# cp2102_esp32.net
KiCad netlist of a schematic drawn in EAGLE
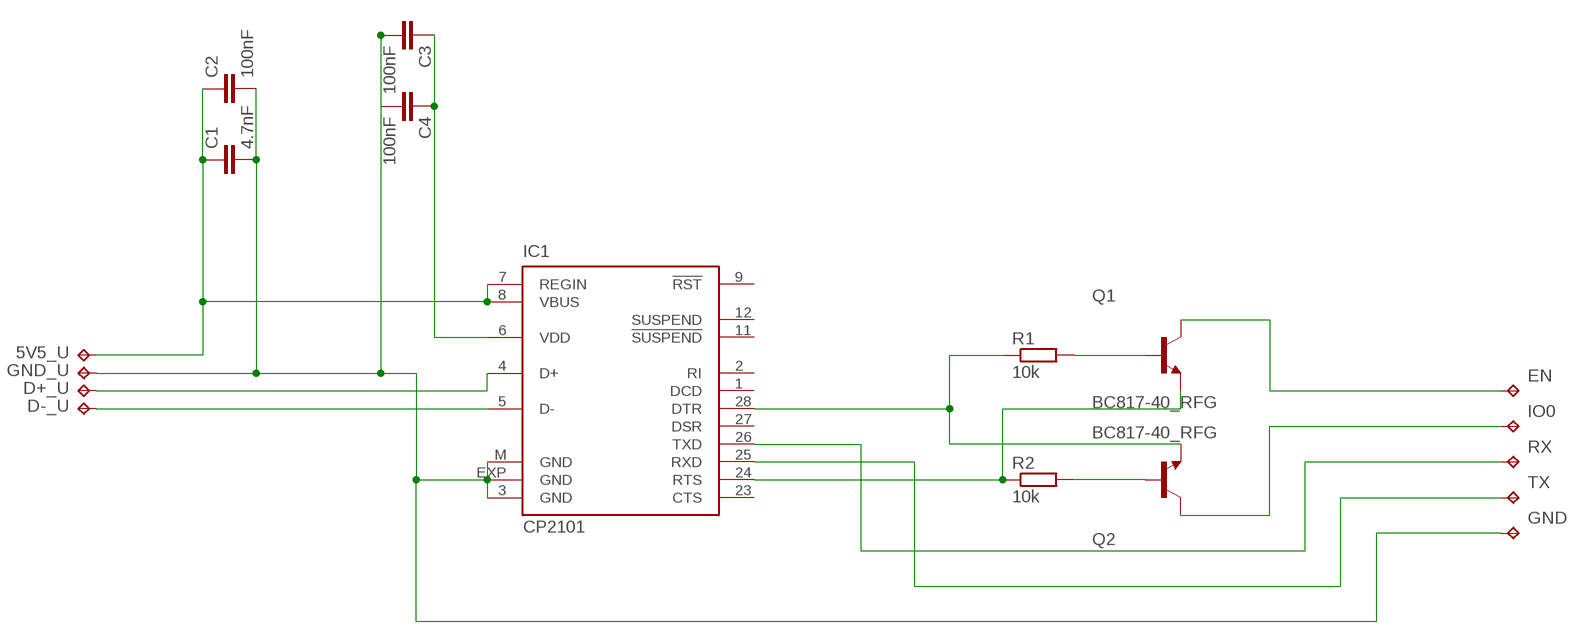
[diagram p0: schematic, sheet 1]

(export (version "E")
  (design (tool "Eeschema 10.0.6"))
  (components
    (comp (ref "5V5_U")
      (value "TPB1,27")
      (footprint "eagle-import:B1,27")
      (libsource (lib "eagle-import") (part "TPB1,27"))
    )
    (comp (ref "C1")
      (value "4.7nF")
      (footprint "eagle-import:C0603")
      (libsource (lib "eagle-import") (part "C-EUC0603"))
    )
    (comp (ref "C2")
      (value "100nF")
      (footprint "eagle-import:C0603")
      (libsource (lib "eagle-import") (part "C-EUC0603"))
    )
    (comp (ref "C3")
      (value "100nF")
      (footprint "eagle-import:C0603")
      (libsource (lib "eagle-import") (part "C-EUC0603"))
    )
    (comp (ref "C4")
      (value "100nF")
      (footprint "eagle-import:C0603")
      (libsource (lib "eagle-import") (part "C-EUC0603"))
    )
    (comp (ref "D+_U")
      (value "TPB1,27")
      (footprint "eagle-import:B1,27")
      (libsource (lib "eagle-import") (part "TPB1,27"))
    )
    (comp (ref "D-_U")
      (value "TPB1,27")
      (footprint "eagle-import:B1,27")
      (libsource (lib "eagle-import") (part "TPB1,27"))
    )
    (comp (ref "EN")
      (value "TPB1,27")
      (footprint "eagle-import:B1,27")
      (libsource (lib "eagle-import") (part "TPB1,27"))
    )
    (comp (ref "GND")
      (value "TPB1,27")
      (footprint "eagle-import:B1,27")
      (libsource (lib "eagle-import") (part "TPB1,27"))
    )
    (comp (ref "GND_U")
      (value "TPB1,27")
      (footprint "eagle-import:B1,27")
      (libsource (lib "eagle-import") (part "TPB1,27"))
    )
    (comp (ref "IC1")
      (value "CP2101")
      (footprint "eagle-import:MLP28")
      (fields (field (name "MF") "FARNELL") (field (name "MPN") "CP2102-GM"))
      (libsource (lib "eagle-import") (part "CP2101"))
    )
    (comp (ref "IO0")
      (value "TPB1,27")
      (footprint "eagle-import:B1,27")
      (libsource (lib "eagle-import") (part "TPB1,27"))
    )
    (comp (ref "Q1")
      (value "BC817-40_RFG")
      (footprint "eagle-import:SOT95P237X112-3N")
      (fields (field (name "MF") "Taiwan Semiconductor") (field (name "MP") "BC817-40 RFG"))
      (libsource (lib "eagle-import") (part "BC817-40_RFG"))
    )
    (comp (ref "Q2")
      (value "BC817-40_RFG")
      (footprint "eagle-import:SOT95P237X112-3N")
      (fields (field (name "MF") "Taiwan Semiconductor") (field (name "MP") "BC817-40 RFG"))
      (libsource (lib "eagle-import") (part "BC817-40_RFG"))
    )
    (comp (ref "R1")
      (value "10k")
      (footprint "eagle-import:R0603")
      (libsource (lib "eagle-import") (part "R-EU_R0603"))
    )
    (comp (ref "R2")
      (value "10k")
      (footprint "eagle-import:R0603")
      (libsource (lib "eagle-import") (part "R-EU_R0603"))
    )
    (comp (ref "RX")
      (value "TPB1,27")
      (footprint "eagle-import:B1,27")
      (libsource (lib "eagle-import") (part "TPB1,27"))
    )
    (comp (ref "TX")
      (value "TPB1,27")
      (footprint "eagle-import:B1,27")
      (libsource (lib "eagle-import") (part "TPB1,27"))
    )
  )
  (nets
    (net (code "1") (name "Net-(C1-Pad2)") (class "Default")
      (node (ref "C1") (pin "2") (pinfunction "2_2") (pintype "passive"))
      (node (ref "C2") (pin "2") (pinfunction "2_2") (pintype "passive"))
      (node (ref "C3") (pin "2") (pinfunction "2_2") (pintype "passive"))
      (node (ref "C4") (pin "2") (pinfunction "2_2") (pintype "passive"))
      (node (ref "GND") (pin "TP") (pinfunction "TP_TP") (pintype "input"))
      (node (ref "GND_U") (pin "TP") (pinfunction "TP_TP") (pintype "input"))
      (node (ref "IC1") (pin "3") (pinfunction "GND_3") (pintype "power_in"))
      (node (ref "IC1") (pin "EXP") (pinfunction "GND_EXP") (pintype "power_in"))
      (node (ref "IC1") (pin "M") (pinfunction "GND_M") (pintype "power_in"))
    )
    (net (code "2") (name "Net-(IC1-D+)") (class "Default")
      (node (ref "D+_U") (pin "TP") (pinfunction "TP_TP") (pintype "input"))
      (node (ref "IC1") (pin "4") (pinfunction "D+_4") (pintype "bidirectional"))
    )
    (net (code "3") (name "Net-(IC1-D-)") (class "Default")
      (node (ref "D-_U") (pin "TP") (pinfunction "TP_TP") (pintype "input"))
      (node (ref "IC1") (pin "5") (pinfunction "D-_5") (pintype "bidirectional"))
    )
    (net (code "4") (name "Net-(IC1-DTR)") (class "Default")
      (node (ref "IC1") (pin "28") (pinfunction "DTR_28") (pintype "output"))
      (node (ref "Q2") (pin "2") (pinfunction "E_2") (pintype "passive"))
      (node (ref "R1") (pin "1") (pinfunction "1_1") (pintype "passive"))
    )
    (net (code "5") (name "Net-(IC1-REGIN)") (class "Default")
      (node (ref "5V5_U") (pin "TP") (pinfunction "TP_TP") (pintype "input"))
      (node (ref "C1") (pin "1") (pinfunction "1_1") (pintype "passive"))
      (node (ref "C2") (pin "1") (pinfunction "1_1") (pintype "passive"))
      (node (ref "IC1") (pin "7") (pinfunction "REGIN_7") (pintype "passive"))
      (node (ref "IC1") (pin "8") (pinfunction "VBUS_8") (pintype "input"))
    )
    (net (code "6") (name "Net-(IC1-RTS)") (class "Default")
      (node (ref "IC1") (pin "24") (pinfunction "RTS_24") (pintype "output"))
      (node (ref "Q1") (pin "2") (pinfunction "E_2") (pintype "passive"))
      (node (ref "R2") (pin "1") (pinfunction "1_1") (pintype "passive"))
    )
    (net (code "7") (name "Net-(IC1-RXD)") (class "Default")
      (node (ref "IC1") (pin "25") (pinfunction "RXD_25") (pintype "input"))
      (node (ref "TX") (pin "TP") (pinfunction "TP_TP") (pintype "input"))
    )
    (net (code "8") (name "Net-(IC1-TXD)") (class "Default")
      (node (ref "IC1") (pin "26") (pinfunction "TXD_26") (pintype "output"))
      (node (ref "RX") (pin "TP") (pinfunction "TP_TP") (pintype "input"))
    )
    (net (code "9") (name "Net-(IC1-VDD)") (class "Default")
      (node (ref "C3") (pin "1") (pinfunction "1_1") (pintype "passive"))
      (node (ref "C4") (pin "1") (pinfunction "1_1") (pintype "passive"))
      (node (ref "IC1") (pin "6") (pinfunction "VDD_6") (pintype "power_in"))
    )
    (net (code "10") (name "Net-(Q1-B)") (class "Default")
      (node (ref "Q1") (pin "1") (pinfunction "B_1") (pintype "passive"))
      (node (ref "R1") (pin "2") (pinfunction "2_2") (pintype "passive"))
    )
    (net (code "11") (name "Net-(Q1-C)") (class "Default")
      (node (ref "EN") (pin "TP") (pinfunction "TP_TP") (pintype "input"))
      (node (ref "Q1") (pin "3") (pinfunction "C_3") (pintype "passive"))
    )
    (net (code "12") (name "Net-(Q2-B)") (class "Default")
      (node (ref "Q2") (pin "1") (pinfunction "B_1") (pintype "passive"))
      (node (ref "R2") (pin "2") (pinfunction "2_2") (pintype "passive"))
    )
    (net (code "13") (name "Net-(Q2-C)") (class "Default")
      (node (ref "IO0") (pin "TP") (pinfunction "TP_TP") (pintype "input"))
      (node (ref "Q2") (pin "3") (pinfunction "C_3") (pintype "passive"))
    )
    (net (code "14") (name "unconnected-(IC1-CTS-Pad23)") (class "Default")
      (node (ref "IC1") (pin "23") (pinfunction "CTS_23") (pintype "input"))
    )
    (net (code "15") (name "unconnected-(IC1-DCD-Pad1)") (class "Default")
      (node (ref "IC1") (pin "1") (pinfunction "DCD_1") (pintype "input"))
    )
    (net (code "16") (name "unconnected-(IC1-DSR-Pad27)") (class "Default")
      (node (ref "IC1") (pin "27") (pinfunction "DSR_27") (pintype "input"))
    )
    (net (code "17") (name "unconnected-(IC1-RI-Pad2)") (class "Default")
      (node (ref "IC1") (pin "2") (pinfunction "RI_2") (pintype "input"))
    )
    (net (code "18") (name "unconnected-(IC1-SUSPEND-Pad12)") (class "Default")
      (node (ref "IC1") (pin "12") (pinfunction "SUSPEND_12") (pintype "output"))
    )
    (net (code "19") (name "unconnected-(IC1-~{RST}-Pad9)") (class "Default")
      (node (ref "IC1") (pin "9") (pinfunction "~{RST}_9") (pintype "bidirectional"))
    )
    (net (code "20") (name "unconnected-(IC1-~{SUSPEND}-Pad11)") (class "Default")
      (node (ref "IC1") (pin "11") (pinfunction "~{SUSPEND}_11") (pintype "output"))
    )
  )
)
